# SCH_Driver_Key_1_3-PCB_2026-01-25.net
KiCad netlist of a schematic drawn in EasyEDA
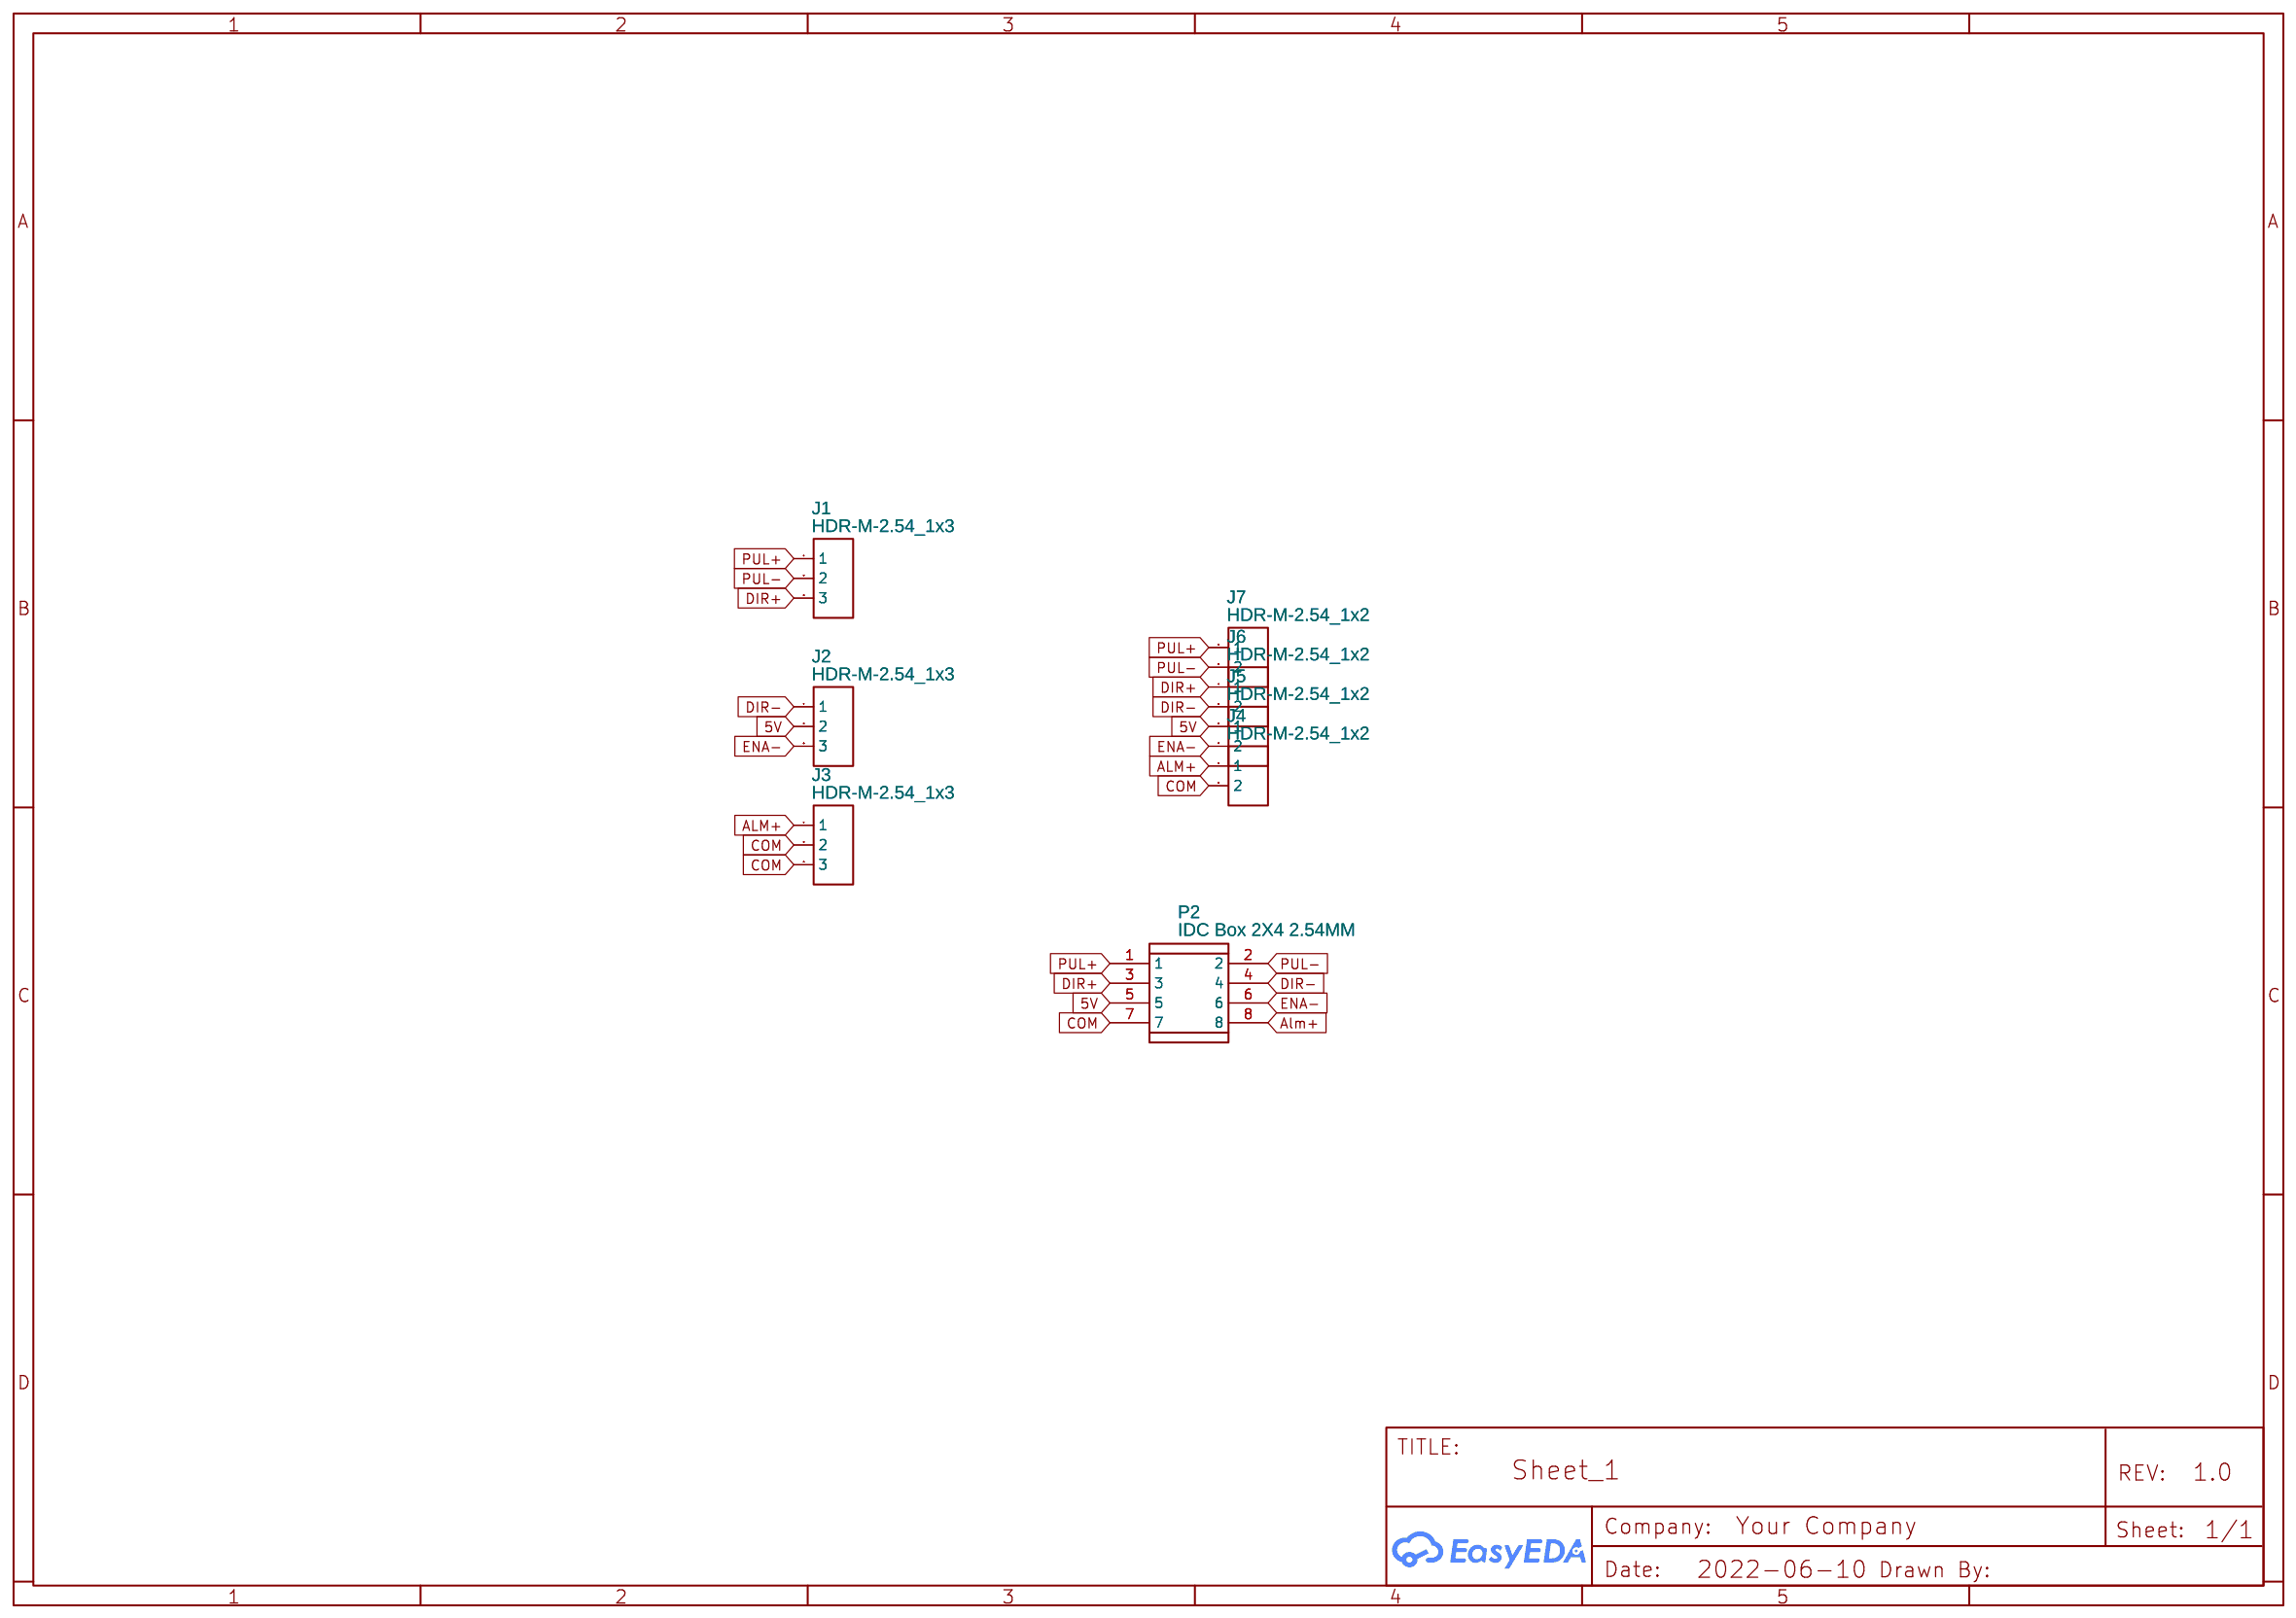
[diagram p0: schematic sheet]

(export (version "E")
  (design (tool "Eeschema 10.0.6"))
  (components
    (comp (ref "J1") (value "HDR-M-2.54_1x3") (libsource (lib "") (part "HDR-M-2.54_1x3")))
    (comp (ref "J2") (value "HDR-M-2.54_1x3") (libsource (lib "") (part "HDR-M-2.54_1x3")))
    (comp (ref "J3") (value "HDR-M-2.54_1x3") (libsource (lib "") (part "HDR-M-2.54_1x3")))
    (comp (ref "J4") (value "HDR-M-2.54_1x2") (libsource (lib "") (part "HDR-M-2.54_1x2")))
    (comp (ref "J5") (value "HDR-M-2.54_1x2") (libsource (lib "") (part "HDR-M-2.54_1x2")))
    (comp (ref "J6") (value "HDR-M-2.54_1x2") (libsource (lib "") (part "HDR-M-2.54_1x2")))
    (comp (ref "J7") (value "HDR-M-2.54_1x2") (libsource (lib "") (part "HDR-M-2.54_1x2")))
    (comp (ref "P2")
      (value "IDC Box 2X4 2.54MM")
      (fields (field (name "Manufacturer Part") "2.54-2*4P弯简牛") (field (name "Manufacturer") "BOOMELE(博穆精密)"))
      (libsource (lib "") (part "IDC Box 2X4 2.54MM"))
    )
  )
  (nets
    (net (code "1") (name "5V") (class "Default")
      (node (ref "J2") (pin "2") (pinfunction "2_2") (pintype "input"))
      (node (ref "J5") (pin "1") (pinfunction "1_1") (pintype "unspecified"))
      (node (ref "P2") (pin "5") (pinfunction "5_5") (pintype "unspecified"))
    )
    (net (code "2") (name "ALM+") (class "Default")
      (node (ref "J3") (pin "1") (pinfunction "1_1") (pintype "input"))
      (node (ref "J4") (pin "1") (pinfunction "1_1") (pintype "unspecified"))
    )
    (net (code "3") (name "Alm+") (class "Default")
      (node (ref "P2") (pin "8") (pinfunction "8_8") (pintype "unspecified"))
    )
    (net (code "4") (name "COM") (class "Default")
      (node (ref "J3") (pin "2") (pinfunction "2_2") (pintype "input"))
      (node (ref "J3") (pin "3") (pinfunction "3_3") (pintype "input"))
      (node (ref "J4") (pin "2") (pinfunction "2_2") (pintype "unspecified"))
      (node (ref "P2") (pin "7") (pinfunction "7_7") (pintype "unspecified"))
    )
    (net (code "5") (name "DIR+") (class "Default")
      (node (ref "J1") (pin "3") (pinfunction "3_3") (pintype "input"))
      (node (ref "J6") (pin "1") (pinfunction "1_1") (pintype "unspecified"))
      (node (ref "P2") (pin "3") (pinfunction "3_3") (pintype "unspecified"))
    )
    (net (code "6") (name "DIR-") (class "Default")
      (node (ref "J2") (pin "1") (pinfunction "1_1") (pintype "input"))
      (node (ref "J6") (pin "2") (pinfunction "2_2") (pintype "unspecified"))
      (node (ref "P2") (pin "4") (pinfunction "4_4") (pintype "unspecified"))
    )
    (net (code "7") (name "ENA-") (class "Default")
      (node (ref "J2") (pin "3") (pinfunction "3_3") (pintype "input"))
      (node (ref "J5") (pin "2") (pinfunction "2_2") (pintype "unspecified"))
      (node (ref "P2") (pin "6") (pinfunction "6_6") (pintype "unspecified"))
    )
    (net (code "8") (name "PUL+") (class "Default")
      (node (ref "J1") (pin "1") (pinfunction "1_1") (pintype "input"))
      (node (ref "J7") (pin "1") (pinfunction "1_1") (pintype "unspecified"))
      (node (ref "P2") (pin "1") (pinfunction "1_1") (pintype "unspecified"))
    )
    (net (code "9") (name "PUL-") (class "Default")
      (node (ref "J1") (pin "2") (pinfunction "2_2") (pintype "input"))
      (node (ref "J7") (pin "2") (pinfunction "2_2") (pintype "unspecified"))
      (node (ref "P2") (pin "2") (pinfunction "2_2") (pintype "unspecified"))
    )
  )
)
